# plp-cd_3a.net
KiCad netlist of a schematic drawn in Altium Designer
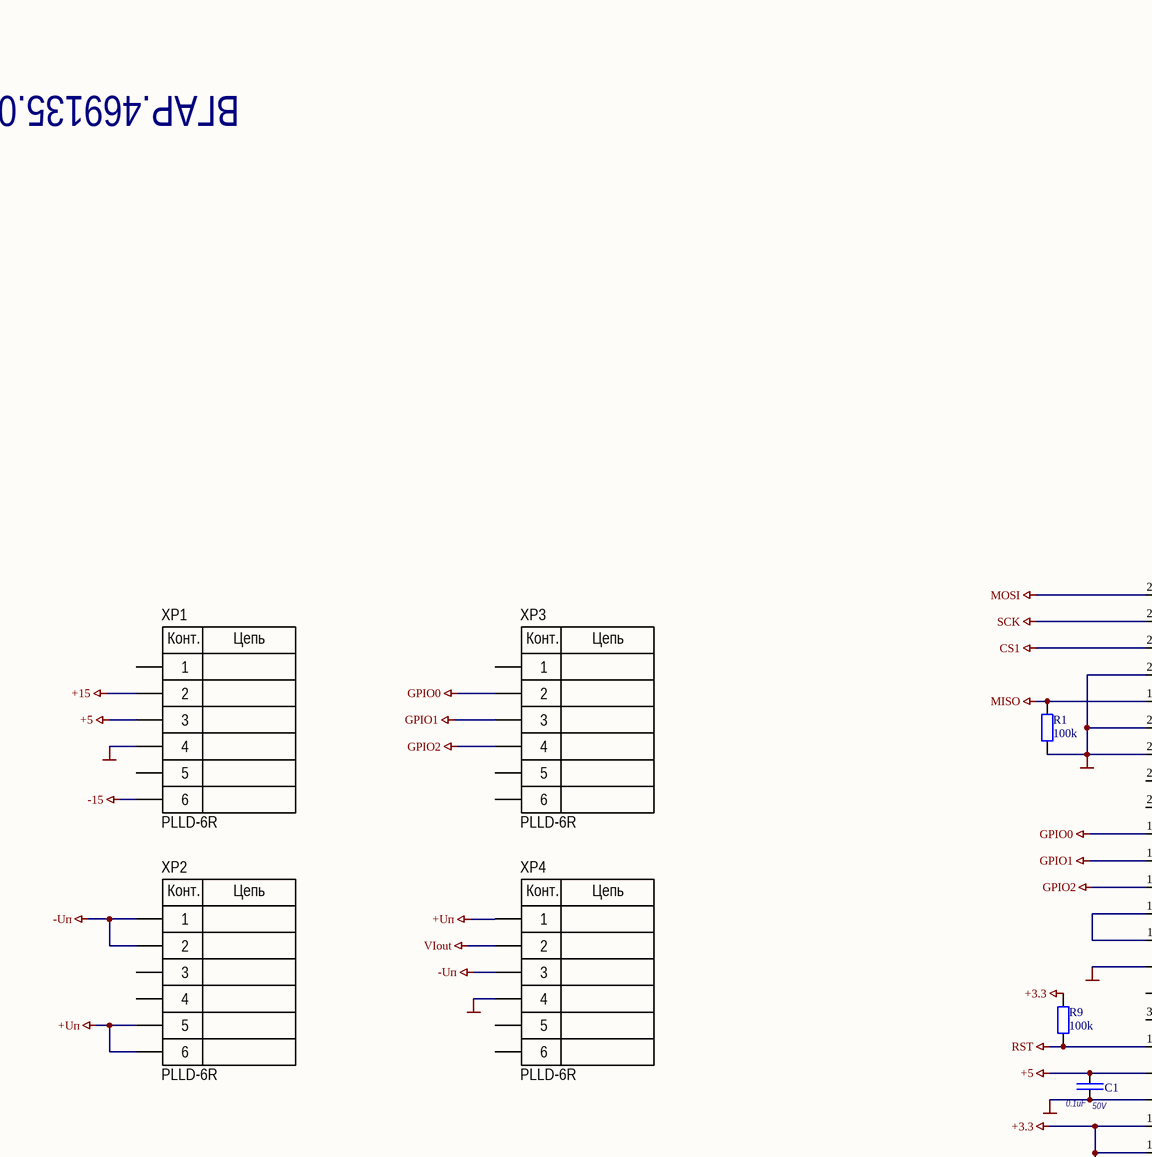
[diagram p0: plp-cd_3a.SchDoc, top left]
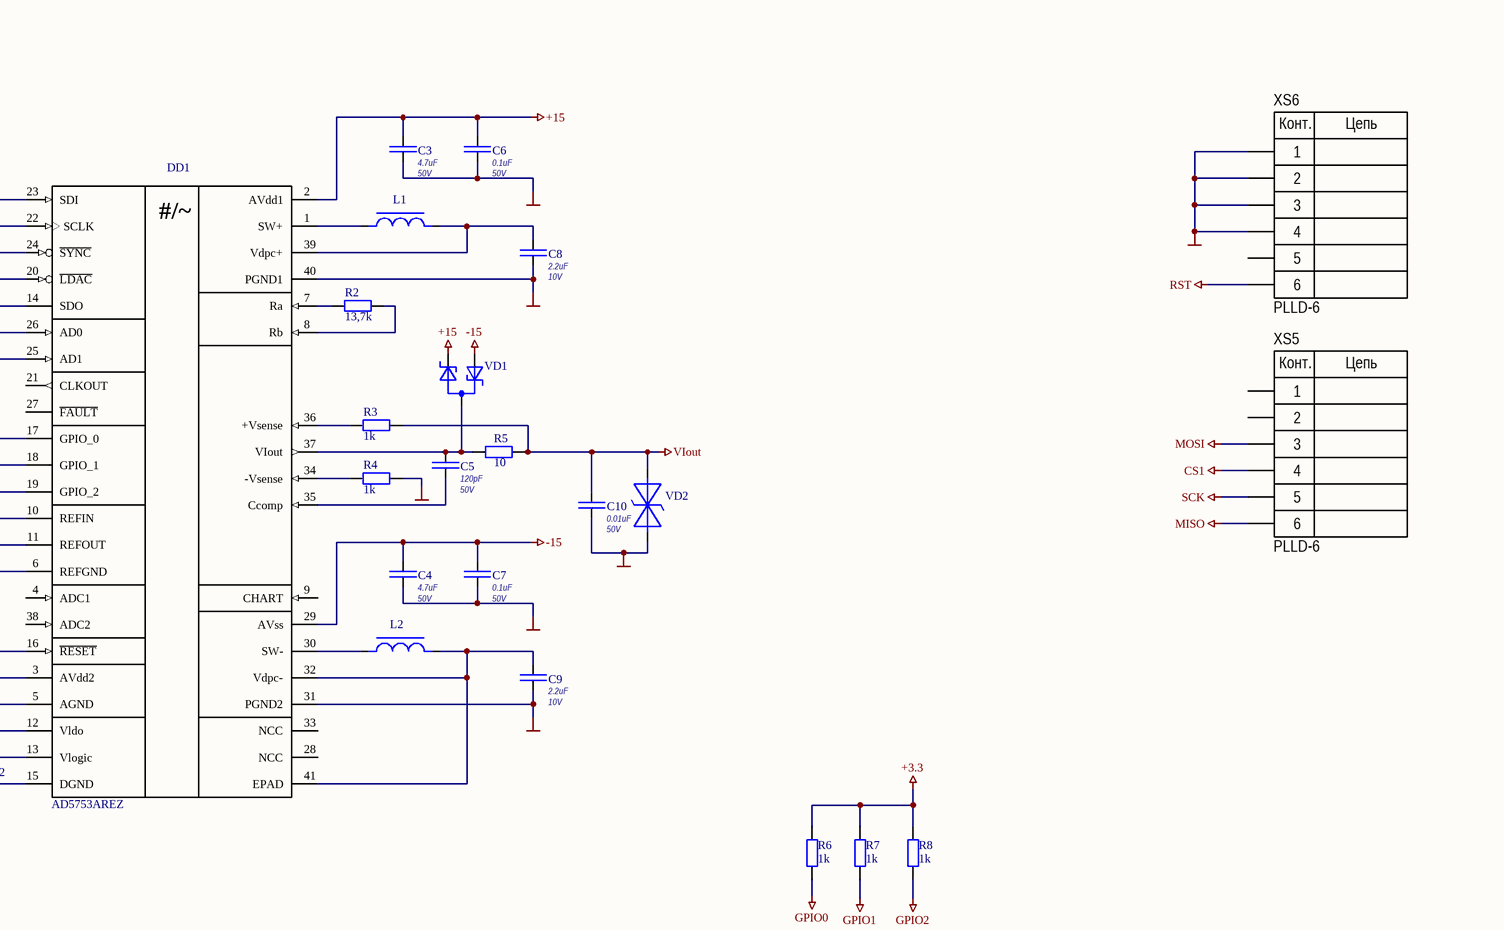
[diagram p1: plp-cd_3a.SchDoc, top right]
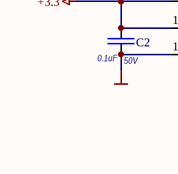
[diagram p2: plp-cd_3a.SchDoc, bottom left]
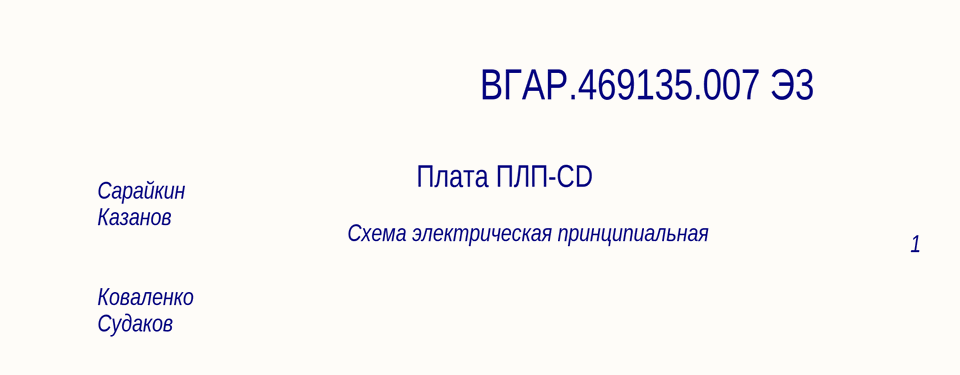
[diagram p3: plp-cd_3a.SchDoc, bottom right]

(export (version "E")
  (design (tool "Eeschema 10.0.6"))
  (components
    (comp (ref "C1")
      (value "0.1uF")
      (footprint "CAPC_0603(1608)X080L")
      (description "Конденсатор")
      (fields
        (field (name "MANUFACTURER") "Murata")
        (field (name "TOLERANCE") "±10%")
        (field (name "RATED DC VOLTAGE") "50V")
      )
      (libsource (lib "Chip Capacitor") (part "Capacitor Ceramic"))
    )
    (comp (ref "C2")
      (value "0.1uF")
      (footprint "CAPC_0603(1608)X080L")
      (description "Конденсатор")
      (fields
        (field (name "MANUFACTURER") "Murata")
        (field (name "TOLERANCE") "±10%")
        (field (name "RATED DC VOLTAGE") "50V")
      )
      (libsource (lib "") (part "Capacitor Ceramic_1"))
    )
    (comp (ref "C3")
      (value "4.7uF")
      (footprint "CAPC_0603(1608)X080L")
      (description "Конденсатор")
      (fields
        (field (name "MANUFACTURER") "Murata")
        (field (name "TOLERANCE") "±10%")
        (field (name "RATED DC VOLTAGE") "50V")
      )
      (libsource (lib "Chip Capacitor") (part "Capacitor Ceramic"))
    )
    (comp (ref "C4")
      (value "4.7uF")
      (footprint "CAPC_0603(1608)X080L")
      (description "Конденсатор")
      (fields
        (field (name "MANUFACTURER") "Murata")
        (field (name "TOLERANCE") "±10%")
        (field (name "RATED DC VOLTAGE") "50V")
      )
      (libsource (lib "Chip Capacitor") (part "Capacitor Ceramic"))
    )
    (comp (ref "C5")
      (value "120pF")
      (footprint "CAPC_0603(1608)X080L")
      (description "Конденсатор")
      (fields
        (field (name "MANUFACTURER") "Murata")
        (field (name "TOLERANCE") "±10%")
        (field (name "RATED DC VOLTAGE") "50V")
      )
      (libsource (lib "Chip Capacitor") (part "Capacitor Ceramic"))
    )
    (comp (ref "C6")
      (value "0.1uF")
      (footprint "CAPC_0603(1608)X080L")
      (description "Конденсатор")
      (fields
        (field (name "MANUFACTURER") "Murata")
        (field (name "TOLERANCE") "±10%")
        (field (name "RATED DC VOLTAGE") "50V")
      )
      (libsource (lib "Chip Capacitor") (part "Capacitor Ceramic"))
    )
    (comp (ref "C7")
      (value "0.1uF")
      (footprint "CAPC_0603(1608)X080L")
      (description "Конденсатор")
      (fields
        (field (name "MANUFACTURER") "Murata")
        (field (name "TOLERANCE") "±10%")
        (field (name "RATED DC VOLTAGE") "50V")
      )
      (libsource (lib "Chip Capacitor") (part "Capacitor Ceramic"))
    )
    (comp (ref "C8")
      (value "2.2uF")
      (footprint "CAPC_0603(1608)X080L")
      (description "Конденсатор")
      (fields
        (field (name "MANUFACTURER") "Murata")
        (field (name "TOLERANCE") "±10%")
        (field (name "RATED DC VOLTAGE") "10V")
      )
      (libsource (lib "Chip Capacitor") (part "Capacitor Ceramic"))
    )
    (comp (ref "C9")
      (value "2.2uF")
      (footprint "CAPC_0603(1608)X080L")
      (description "Конденсатор")
      (fields
        (field (name "MANUFACTURER") "Murata")
        (field (name "TOLERANCE") "±10%")
        (field (name "RATED DC VOLTAGE") "10V")
      )
      (libsource (lib "Chip Capacitor") (part "Capacitor Ceramic"))
    )
    (comp (ref "C10")
      (value "0.01uF")
      (footprint "CAPC_0603(1608)X080L")
      (description "Конденсатор")
      (fields
        (field (name "MANUFACTURER") "Murata")
        (field (name "TOLERANCE") "±10%")
        (field (name "RATED DC VOLTAGE") "50V")
      )
      (libsource (lib "Chip Capacitor") (part "Capacitor Ceramic"))
    )
    (comp (ref "DD1")
      (value "AD5753AREZ")
      (footprint "CP-40-15")
      (description "Микросхема")
      (fields (field (name "MANUFACTURER") "Analog Devices"))
      (libsource (lib "AD DAC") (part "AD5753"))
    )
    (comp (ref "L1")
      (value "CDRH4D28")
      (footprint "CDRH4D28_INDP5050X28N")
      (libsource (lib "Sumida Power Inductor") (part "CDRH4D28"))
    )
    (comp (ref "L2")
      (value "CDRH4D28")
      (footprint "CDRH4D28_INDP5050X28N")
      (libsource (lib "Sumida Power Inductor") (part "CDRH4D28"))
    )
    (comp (ref "R1")
      (value "100k")
      (footprint "RESC1608(0603)X04L")
      (description "Резистор")
      (fields (field (name "MANUFACTURER") "Bourns") (field (name "POWER") "1/10 Вт"))
      (libsource (lib "") (part "R0603L_2"))
    )
    (comp (ref "R2")
      (value "13,7k")
      (footprint "RESC1608(0603)X04L")
      (description "Резистор")
      (fields (field (name "MANUFACTURER") "Bourns") (field (name "POWER") "1/10 Вт"))
      (libsource (lib "Chip Resistor") (part "R0603L"))
    )
    (comp (ref "R3")
      (value "1k")
      (footprint "RESC1608(0603)X04L")
      (description "Резистор")
      (fields (field (name "MANUFACTURER") "Bourns") (field (name "POWER") "1/10 Вт"))
      (libsource (lib "Chip Resistor") (part "R0603L"))
    )
    (comp (ref "R4")
      (value "1k")
      (footprint "RESC1608(0603)X04L")
      (description "Резистор")
      (fields (field (name "MANUFACTURER") "Bourns") (field (name "POWER") "1/10 Вт"))
      (libsource (lib "Chip Resistor") (part "R0603L"))
    )
    (comp (ref "R5")
      (value "10")
      (footprint "RESC1608(0603)X04L")
      (description "Резистор")
      (fields (field (name "MANUFACTURER") "Bourns") (field (name "POWER") "1/10 Вт"))
      (libsource (lib "Chip Resistor") (part "R0603L"))
    )
    (comp (ref "R6")
      (value "1k")
      (footprint "RESC1608(0603)X04L")
      (description "Резистор")
      (fields (field (name "MANUFACTURER") "Bourns") (field (name "POWER") "1/10 Вт"))
      (libsource (lib "") (part "R0603L_1"))
    )
    (comp (ref "R7")
      (value "1k")
      (footprint "RESC1608(0603)X04L")
      (description "Резистор")
      (fields (field (name "MANUFACTURER") "Bourns") (field (name "POWER") "1/10 Вт"))
      (libsource (lib "") (part "R0603L_1"))
    )
    (comp (ref "R8")
      (value "1k")
      (footprint "RESC1608(0603)X04L")
      (description "Резистор")
      (fields (field (name "MANUFACTURER") "Bourns") (field (name "POWER") "1/10 Вт"))
      (libsource (lib "") (part "R0603L_1"))
    )
    (comp (ref "R9")
      (value "100k")
      (footprint "RESC1608(0603)X04L")
      (description "Резистор")
      (fields (field (name "MANUFACTURER") "Bourns") (field (name "POWER") "1/10 Вт"))
      (libsource (lib "") (part "R0603L_2"))
    )
    (comp (ref "VD1")
      (value "BAT54SW")
      (footprint "SC-70")
      (description "Сборка диодная")
      (fields (field (name "MANUFACTURER") "NXP") (field (name "REPLACEMENTPART1PARTNUMBER") "BAT54SWT1G"))
      (libsource (lib "NXP Diodes") (part "BAT54SW"))
    )
    (comp (ref "VD2")
      (value "Transil Bi")
      (footprint "SMB - UNI")
      (description "TVS Диод")
      (fields (field (name "MANUFACTURER") "ST Microelectronics"))
      (libsource (lib "ST Protection Diodes") (part "Transil Bi"))
    )
    (comp (ref "XP1")
      (value "PLLD-6R")
      (footprint "CON: PLL-6(2x3R1.27male)")
      (description "Step 1.27 R")
      (libsource (lib "connector") (part "PLLD-6R(Male)"))
    )
    (comp (ref "XP2")
      (value "PLLD-6R")
      (footprint "CON: PLL-6(2x3R1.27male)")
      (description "Step 1.27 R")
      (libsource (lib "connector") (part "PLLD-6R(Male)"))
    )
    (comp (ref "XP3")
      (value "PLLD-6R")
      (footprint "CON: PLL-6(2x3R1.27male)")
      (description "Step 1.27 R")
      (libsource (lib "connector") (part "PLLD-6R(Male)"))
    )
    (comp (ref "XP4")
      (value "PLLD-6R")
      (footprint "CON: PLL-6(2x3R1.27male)")
      (description "Step 1.27 R")
      (libsource (lib "connector") (part "PLLD-6R(Male)"))
    )
    (comp (ref "XS5")
      (value "PLLD-6")
      (footprint "CON: PLL-6(2x3R1.27female)")
      (description "Step 1.27")
      (libsource (lib "connector") (part "PLLD-6(Female)"))
    )
    (comp (ref "XS6")
      (value "PLLD-6")
      (footprint "CON: PLL-6(2x3R1.27female)")
      (description "Step 1.27")
      (libsource (lib "connector") (part "PLLD-6(Female)"))
    )
  )
  (nets
    (net (code "1") (name "+3.3") (class "Default")
      (node (ref "C2") (pin "2") (pinfunction "2_2") (pintype "passive"))
      (node (ref "DD1") (pin "12") (pinfunction "Vldo_12") (pintype "power_in"))
      (node (ref "DD1") (pin "13") (pinfunction "Vlogic_13") (pintype "power_in"))
      (node (ref "R6") (pin "2") (pinfunction "2_2") (pintype "passive"))
      (node (ref "R7") (pin "2") (pinfunction "2_2") (pintype "passive"))
      (node (ref "R8") (pin "2") (pinfunction "2_2") (pintype "passive"))
      (node (ref "R9") (pin "1") (pinfunction "1_1") (pintype "passive"))
    )
    (net (code "2") (name "+5") (class "Default")
      (node (ref "C1") (pin "2") (pinfunction "2_2") (pintype "passive"))
      (node (ref "DD1") (pin "3") (pinfunction "AVdd2_3") (pintype "power_in"))
      (node (ref "XP1") (pin "3") (pinfunction "3_3") (pintype "passive"))
    )
    (net (code "3") (name "+15") (class "Default")
      (node (ref "C3") (pin "2") (pinfunction "2_2") (pintype "passive"))
      (node (ref "C6") (pin "2") (pinfunction "2_2") (pintype "passive"))
      (node (ref "DD1") (pin "2") (pinfunction "AVdd1_2") (pintype "power_in"))
      (node (ref "VD1") (pin "2") (pinfunction "C_2") (pintype "passive"))
      (node (ref "XP1") (pin "2") (pinfunction "2_2") (pintype "passive"))
    )
    (net (code "4") (name "+Uп") (class "Default")
      (node (ref "XP2") (pin "5") (pinfunction "5_5") (pintype "passive"))
      (node (ref "XP2") (pin "6") (pinfunction "6_6") (pintype "passive"))
      (node (ref "XP4") (pin "1") (pinfunction "1_1") (pintype "passive"))
    )
    (net (code "5") (name "-15") (class "Default")
      (node (ref "C4") (pin "2") (pinfunction "2_2") (pintype "passive"))
      (node (ref "C7") (pin "2") (pinfunction "2_2") (pintype "passive"))
      (node (ref "DD1") (pin "29") (pinfunction "AVss_29") (pintype "power_in"))
      (node (ref "VD1") (pin "1") (pinfunction "A_1") (pintype "passive"))
      (node (ref "XP1") (pin "6") (pinfunction "6_6") (pintype "passive"))
    )
    (net (code "6") (name "-Uп") (class "Default")
      (node (ref "XP2") (pin "1") (pinfunction "1_1") (pintype "passive"))
      (node (ref "XP2") (pin "2") (pinfunction "2_2") (pintype "passive"))
      (node (ref "XP4") (pin "3") (pinfunction "3_3") (pintype "passive"))
    )
    (net (code "7") (name "CS1") (class "Default")
      (node (ref "DD1") (pin "24") (pinfunction "~{SYNC}_24") (pintype "input"))
      (node (ref "XS5") (pin "4") (pinfunction "4_4") (pintype "passive"))
    )
    (net (code "8") (name "GND") (class "Default")
      (node (ref "C1") (pin "1") (pinfunction "1_1") (pintype "passive"))
      (node (ref "C10") (pin "1") (pinfunction "1_1") (pintype "passive"))
      (node (ref "C2") (pin "1") (pinfunction "1_1") (pintype "passive"))
      (node (ref "C3") (pin "1") (pinfunction "1_1") (pintype "passive"))
      (node (ref "C4") (pin "1") (pinfunction "1_1") (pintype "passive"))
      (node (ref "C6") (pin "1") (pinfunction "1_1") (pintype "passive"))
      (node (ref "C7") (pin "1") (pinfunction "1_1") (pintype "passive"))
      (node (ref "C8") (pin "1") (pinfunction "1_1") (pintype "passive"))
      (node (ref "C9") (pin "1") (pinfunction "1_1") (pintype "passive"))
      (node (ref "DD1") (pin "15") (pinfunction "DGND_15") (pintype "power_in"))
      (node (ref "DD1") (pin "20") (pinfunction "~{LDAC}_20") (pintype "input"))
      (node (ref "DD1") (pin "25") (pinfunction "AD1_25") (pintype "input"))
      (node (ref "DD1") (pin "26") (pinfunction "AD0_26") (pintype "input"))
      (node (ref "DD1") (pin "31") (pinfunction "PGND2_31") (pintype "power_in"))
      (node (ref "DD1") (pin "40") (pinfunction "PGND1_40") (pintype "power_in"))
      (node (ref "DD1") (pin "5") (pinfunction "AGND_5") (pintype "power_in"))
      (node (ref "DD1") (pin "6") (pinfunction "REFGND_6") (pintype "power_in"))
      (node (ref "R1") (pin "2") (pinfunction "2_2") (pintype "passive"))
      (node (ref "R4") (pin "2") (pinfunction "2_2") (pintype "passive"))
      (node (ref "VD2") (pin "1") (pinfunction "C_1") (pintype "passive"))
      (node (ref "XP1") (pin "4") (pinfunction "4_4") (pintype "passive"))
      (node (ref "XP4") (pin "4") (pinfunction "4_4") (pintype "passive"))
      (node (ref "XS6") (pin "1") (pinfunction "1_1") (pintype "passive"))
      (node (ref "XS6") (pin "2") (pinfunction "2_2") (pintype "passive"))
      (node (ref "XS6") (pin "3") (pinfunction "3_3") (pintype "passive"))
      (node (ref "XS6") (pin "4") (pinfunction "4_4") (pintype "passive"))
    )
    (net (code "9") (name "GPIO0") (class "Default")
      (node (ref "DD1") (pin "17") (pinfunction "GPIO_0_17") (pintype "passive"))
      (node (ref "R6") (pin "1") (pinfunction "1_1") (pintype "passive"))
      (node (ref "XP3") (pin "2") (pinfunction "2_2") (pintype "passive"))
    )
    (net (code "10") (name "GPIO1") (class "Default")
      (node (ref "DD1") (pin "18") (pinfunction "GPIO_1_18") (pintype "passive"))
      (node (ref "R7") (pin "1") (pinfunction "1_1") (pintype "passive"))
      (node (ref "XP3") (pin "3") (pinfunction "3_3") (pintype "passive"))
    )
    (net (code "11") (name "GPIO2") (class "Default")
      (node (ref "DD1") (pin "19") (pinfunction "GPIO_2_19") (pintype "passive"))
      (node (ref "R8") (pin "1") (pinfunction "1_1") (pintype "passive"))
      (node (ref "XP3") (pin "4") (pinfunction "4_4") (pintype "passive"))
    )
    (net (code "12") (name "MISO") (class "Default")
      (node (ref "DD1") (pin "14") (pinfunction "SDO_14") (pintype "open_collector"))
      (node (ref "R1") (pin "1") (pinfunction "1_1") (pintype "passive"))
      (node (ref "XS5") (pin "6") (pinfunction "6_6") (pintype "passive"))
    )
    (net (code "13") (name "MOSI") (class "Default")
      (node (ref "DD1") (pin "23") (pinfunction "SDI_23") (pintype "input"))
      (node (ref "XS5") (pin "3") (pinfunction "3_3") (pintype "passive"))
    )
    (net (code "14") (name "Net-(DD1-+Vsense)") (class "Default")
      (node (ref "DD1") (pin "36") (pinfunction "+Vsense_36") (pintype "input"))
      (node (ref "R3") (pin "1") (pinfunction "1_1") (pintype "passive"))
    )
    (net (code "15") (name "Net-(DD1--Vsense)") (class "Default")
      (node (ref "DD1") (pin "34") (pinfunction "-Vsense_34") (pintype "input"))
      (node (ref "R4") (pin "1") (pinfunction "1_1") (pintype "passive"))
    )
    (net (code "16") (name "Net-(DD1-Ccomp)") (class "Default")
      (node (ref "C5") (pin "1") (pinfunction "1_1") (pintype "passive"))
      (node (ref "DD1") (pin "35") (pinfunction "Ccomp_35") (pintype "input"))
    )
    (net (code "17") (name "Net-(DD1-EPAD)") (class "Default")
      (node (ref "C9") (pin "2") (pinfunction "2_2") (pintype "passive"))
      (node (ref "DD1") (pin "32") (pinfunction "Vdpc-_32") (pintype "power_in"))
      (node (ref "DD1") (pin "41") (pinfunction "EPAD_41") (pintype "passive"))
      (node (ref "L2") (pin "2") (pinfunction "2_2") (pintype "passive"))
    )
    (net (code "18") (name "Net-(DD1-REFIN)") (class "Default")
      (node (ref "DD1") (pin "10") (pinfunction "REFIN_10") (pintype "passive"))
      (node (ref "DD1") (pin "11") (pinfunction "REFOUT_11") (pintype "power_in"))
    )
    (net (code "19") (name "Net-(DD1-Ra)") (class "Default")
      (node (ref "DD1") (pin "7") (pinfunction "Ra_7") (pintype "input"))
      (node (ref "R2") (pin "1") (pinfunction "1_1") (pintype "passive"))
    )
    (net (code "20") (name "Net-(DD1-Rb)") (class "Default")
      (node (ref "DD1") (pin "8") (pinfunction "Rb_8") (pintype "input"))
      (node (ref "R2") (pin "2") (pinfunction "2_2") (pintype "passive"))
    )
    (net (code "21") (name "Net-(DD1-SW+)") (class "Default")
      (node (ref "DD1") (pin "1") (pinfunction "SW+_1") (pintype "power_in"))
      (node (ref "L1") (pin "1") (pinfunction "1_1") (pintype "passive"))
    )
    (net (code "22") (name "Net-(DD1-SW-)") (class "Default")
      (node (ref "DD1") (pin "30") (pinfunction "SW-_30") (pintype "power_in"))
      (node (ref "L2") (pin "1") (pinfunction "1_1") (pintype "passive"))
    )
    (net (code "23") (name "Net-(DD1-VIout)") (class "Default")
      (node (ref "C5") (pin "2") (pinfunction "2_2") (pintype "passive"))
      (node (ref "DD1") (pin "37") (pinfunction "VIout_37") (pintype "output"))
      (node (ref "R5") (pin "1") (pinfunction "1_1") (pintype "passive"))
      (node (ref "VD1") (pin "3") (pinfunction "OAC_3") (pintype "passive"))
    )
    (net (code "24") (name "Net-(DD1-Vdpc+)") (class "Default")
      (node (ref "C8") (pin "2") (pinfunction "2_2") (pintype "passive"))
      (node (ref "DD1") (pin "39") (pinfunction "Vdpc+_39") (pintype "power_in"))
      (node (ref "L1") (pin "2") (pinfunction "2_2") (pintype "passive"))
    )
    (net (code "25") (name "RST") (class "Default")
      (node (ref "DD1") (pin "16") (pinfunction "~{RESET}_16") (pintype "input"))
      (node (ref "R9") (pin "2") (pinfunction "2_2") (pintype "passive"))
      (node (ref "XS6") (pin "6") (pinfunction "6_6") (pintype "passive"))
    )
    (net (code "26") (name "SCK") (class "Default")
      (node (ref "DD1") (pin "22") (pinfunction "SCLK_22") (pintype "input"))
      (node (ref "XS5") (pin "5") (pinfunction "5_5") (pintype "passive"))
    )
    (net (code "27") (name "VIout") (class "Default")
      (node (ref "C10") (pin "2") (pinfunction "2_2") (pintype "passive"))
      (node (ref "R3") (pin "2") (pinfunction "2_2") (pintype "passive"))
      (node (ref "R5") (pin "2") (pinfunction "2_2") (pintype "passive"))
      (node (ref "VD2") (pin "2") (pinfunction "A_2") (pintype "passive"))
      (node (ref "XP4") (pin "2") (pinfunction "2_2") (pintype "passive"))
    )
    (net (code "28") (name "unconnected-(DD1-ADC1-Pad4)") (class "Default")
      (node (ref "DD1") (pin "4") (pinfunction "ADC1_4") (pintype "input"))
    )
    (net (code "29") (name "unconnected-(DD1-ADC2-Pad38)") (class "Default")
      (node (ref "DD1") (pin "38") (pinfunction "ADC2_38") (pintype "input"))
    )
    (net (code "30") (name "unconnected-(DD1-CHART-Pad9)") (class "Default")
      (node (ref "DD1") (pin "9") (pinfunction "CHART_9") (pintype "input"))
    )
    (net (code "31") (name "unconnected-(DD1-CLKOUT-Pad21)") (class "Default")
      (node (ref "DD1") (pin "21") (pinfunction "CLKOUT_21") (pintype "output"))
    )
    (net (code "32") (name "unconnected-(DD1-NCC-Pad28)") (class "Default")
      (node (ref "DD1") (pin "28") (pinfunction "NCC_28") (pintype "passive"))
    )
    (net (code "33") (name "unconnected-(DD1-NCC-Pad33)") (class "Default")
      (node (ref "DD1") (pin "33") (pinfunction "NCC_33") (pintype "passive"))
    )
    (net (code "34") (name "unconnected-(DD1-~{FAULT}-Pad27)") (class "Default")
      (node (ref "DD1") (pin "27") (pinfunction "~{FAULT}_27") (pintype "open_collector"))
    )
    (net (code "35") (name "unconnected-(XP1-Pad1)") (class "Default")
      (node (ref "XP1") (pin "1") (pinfunction "1_1") (pintype "passive"))
    )
    (net (code "36") (name "unconnected-(XP1-Pad5)") (class "Default")
      (node (ref "XP1") (pin "5") (pinfunction "5_5") (pintype "passive"))
    )
    (net (code "37") (name "unconnected-(XP2-Pad3)") (class "Default")
      (node (ref "XP2") (pin "3") (pinfunction "3_3") (pintype "passive"))
    )
    (net (code "38") (name "unconnected-(XP2-Pad4)") (class "Default")
      (node (ref "XP2") (pin "4") (pinfunction "4_4") (pintype "passive"))
    )
    (net (code "39") (name "unconnected-(XP3-Pad1)") (class "Default")
      (node (ref "XP3") (pin "1") (pinfunction "1_1") (pintype "passive"))
    )
    (net (code "40") (name "unconnected-(XP3-Pad5)") (class "Default")
      (node (ref "XP3") (pin "5") (pinfunction "5_5") (pintype "passive"))
    )
    (net (code "41") (name "unconnected-(XP3-Pad6)") (class "Default")
      (node (ref "XP3") (pin "6") (pinfunction "6_6") (pintype "passive"))
    )
    (net (code "42") (name "unconnected-(XP4-Pad5)") (class "Default")
      (node (ref "XP4") (pin "5") (pinfunction "5_5") (pintype "passive"))
    )
    (net (code "43") (name "unconnected-(XP4-Pad6)") (class "Default")
      (node (ref "XP4") (pin "6") (pinfunction "6_6") (pintype "passive"))
    )
    (net (code "44") (name "unconnected-(XS5-Pad1)") (class "Default")
      (node (ref "XS5") (pin "1") (pinfunction "1_1") (pintype "passive"))
    )
    (net (code "45") (name "unconnected-(XS5-Pad2)") (class "Default")
      (node (ref "XS5") (pin "2") (pinfunction "2_2") (pintype "passive"))
    )
    (net (code "46") (name "unconnected-(XS6-Pad5)") (class "Default")
      (node (ref "XS6") (pin "5") (pinfunction "5_5") (pintype "passive"))
    )
  )
)
